# batterytester.net
KiCad netlist of a schematic drawn in EAGLE
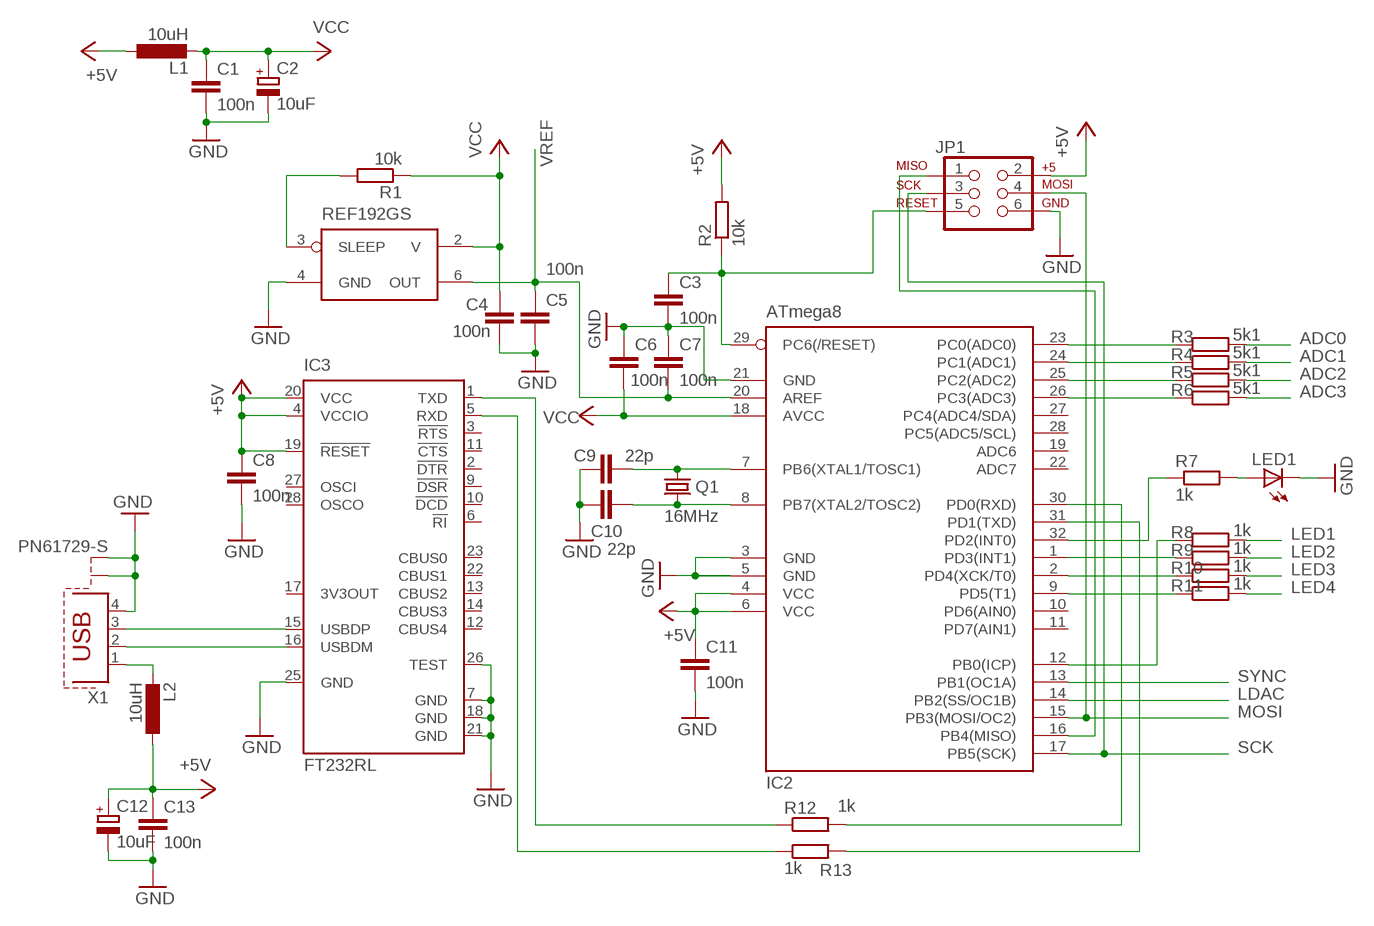
[diagram p0: schematic, sheet 1]
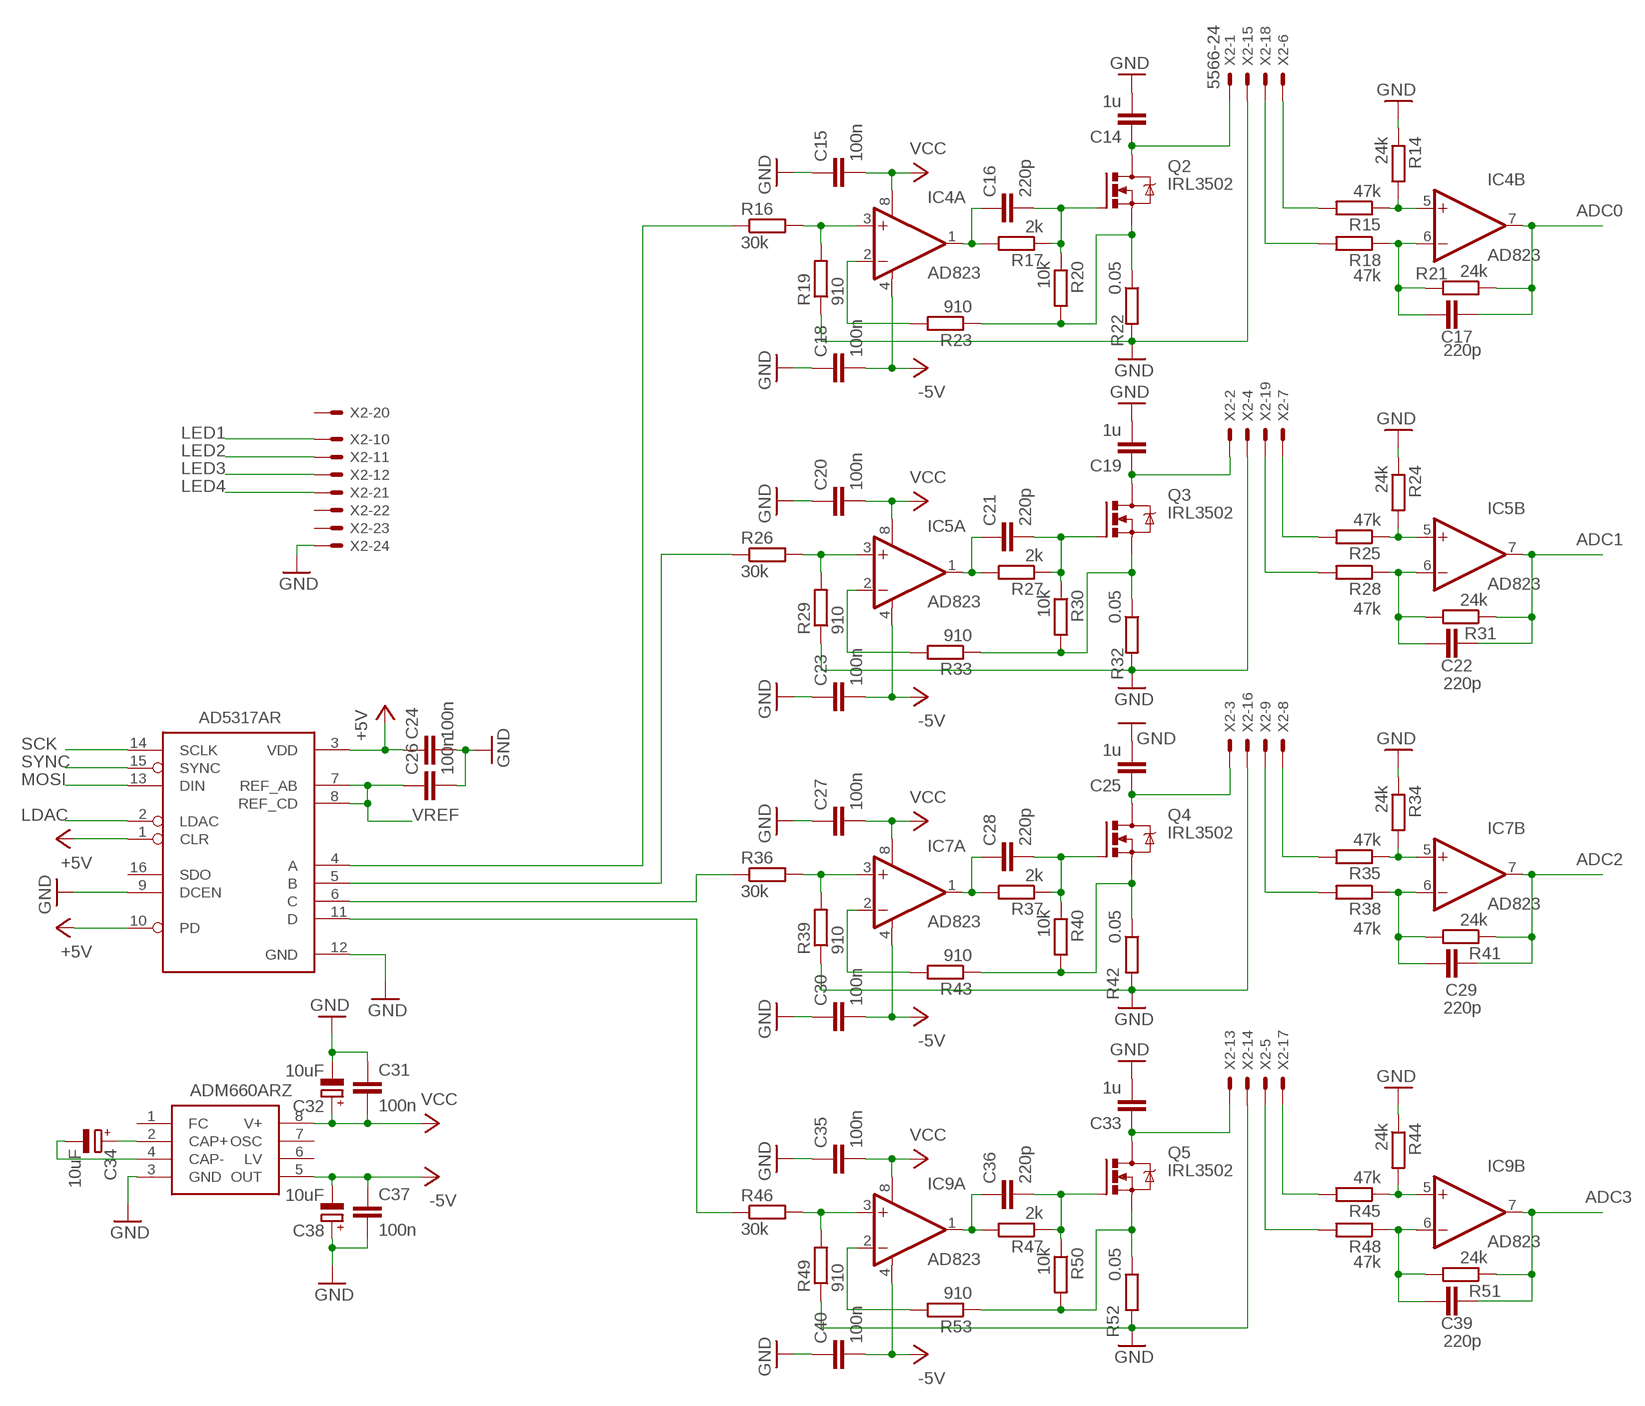
[diagram p1: schematic, sheet 2]

(export (version "E")
  (design (tool "Eeschema 10.0.6"))
  (components
    (comp (ref "C1")
      (value "100n")
      (footprint "eagle-import:C0805")
      (libsource (lib "eagle-import") (part "C-EUC0805"))
    )
    (comp (ref "C2")
      (value "10uF")
      (footprint "eagle-import:SMC_B")
      (libsource (lib "eagle-import") (part "CPOL-EUSMCB"))
    )
    (comp (ref "C3")
      (value "100n")
      (footprint "eagle-import:C0805")
      (libsource (lib "eagle-import") (part "C-EUC0805"))
    )
    (comp (ref "C4")
      (value "100n")
      (footprint "eagle-import:C0805")
      (libsource (lib "eagle-import") (part "C-EUC0805"))
    )
    (comp (ref "C5")
      (value "100n")
      (footprint "eagle-import:C0805")
      (libsource (lib "eagle-import") (part "C-EUC0805"))
    )
    (comp (ref "C6")
      (value "100n")
      (footprint "eagle-import:C0805")
      (libsource (lib "eagle-import") (part "C-EUC0805"))
    )
    (comp (ref "C7")
      (value "100n")
      (footprint "eagle-import:C0805")
      (libsource (lib "eagle-import") (part "C-EUC0805"))
    )
    (comp (ref "C8")
      (value "100n")
      (footprint "eagle-import:C0805")
      (libsource (lib "eagle-import") (part "C-EUC0805"))
    )
    (comp (ref "C9")
      (value "22p")
      (footprint "eagle-import:C0805")
      (libsource (lib "eagle-import") (part "C-EUC0805"))
    )
    (comp (ref "C10")
      (value "22p")
      (footprint "eagle-import:C0805")
      (libsource (lib "eagle-import") (part "C-EUC0805"))
    )
    (comp (ref "C11")
      (value "100n")
      (footprint "eagle-import:C0805")
      (libsource (lib "eagle-import") (part "C-EUC0805"))
    )
    (comp (ref "C12")
      (value "10uF")
      (footprint "eagle-import:SMC_B")
      (libsource (lib "eagle-import") (part "CPOL-EUSMCB"))
    )
    (comp (ref "C13")
      (value "100n")
      (footprint "eagle-import:C0805")
      (libsource (lib "eagle-import") (part "C-EUC0805"))
    )
    (comp (ref "IC1")
      (value "REF192GS")
      (footprint "eagle-import:SO8")
      (libsource (lib "eagle-import") (part "REF192"))
    )
    (comp (ref "IC2")
      (value "ATmega8")
      (footprint "eagle-import:TQFP32-08")
      (libsource (lib "eagle-import") (part "MEGA8-AI"))
    )
    (comp (ref "IC3")
      (value "FT232RL")
      (footprint "eagle-import:SSOP28")
      (libsource (lib "eagle-import") (part "FT232RL"))
    )
    (comp (ref "JP1")
      (value "AVR_SPI_PRG_6NS")
      (footprint "eagle-import:2X3-NS")
      (libsource (lib "eagle-import") (part "AVR_SPI_PRG_6NS"))
    )
    (comp (ref "L1")
      (value "10uH")
      (footprint "eagle-import:L1812")
      (libsource (lib "eagle-import") (part "L-EUL1812"))
    )
    (comp (ref "L2")
      (value "10uH")
      (footprint "eagle-import:L1812")
      (libsource (lib "eagle-import") (part "L-EUL1812"))
    )
    (comp (ref "LED1")
      (value "LED3MM")
      (footprint "eagle-import:LED3MM")
      (libsource (lib "eagle-import") (part "LED3MM"))
    )
    (comp (ref "Q1")
      (value "16MHz")
      (footprint "eagle-import:HC49_S")
      (libsource (lib "eagle-import") (part "CRYSTALHC49S"))
    )
    (comp (ref "R1")
      (value "10k")
      (footprint "eagle-import:R0805")
      (libsource (lib "eagle-import") (part "R-EU_R0805"))
    )
    (comp (ref "R2")
      (value "10k")
      (footprint "eagle-import:R0805")
      (libsource (lib "eagle-import") (part "R-EU_R0805"))
    )
    (comp (ref "R3")
      (value "5k1")
      (footprint "eagle-import:R0805")
      (libsource (lib "eagle-import") (part "R-EU_R0805"))
    )
    (comp (ref "R4")
      (value "5k1")
      (footprint "eagle-import:R0805")
      (libsource (lib "eagle-import") (part "R-EU_R0805"))
    )
    (comp (ref "R5")
      (value "5k1")
      (footprint "eagle-import:R0805")
      (libsource (lib "eagle-import") (part "R-EU_R0805"))
    )
    (comp (ref "R6")
      (value "5k1")
      (footprint "eagle-import:R0805")
      (libsource (lib "eagle-import") (part "R-EU_R0805"))
    )
    (comp (ref "R7")
      (value "1k")
      (footprint "eagle-import:R0805")
      (libsource (lib "eagle-import") (part "R-EU_R0805"))
    )
    (comp (ref "R8")
      (value "1k")
      (footprint "eagle-import:R0805")
      (libsource (lib "eagle-import") (part "R-EU_R0805"))
    )
    (comp (ref "R9")
      (value "1k")
      (footprint "eagle-import:R0805")
      (libsource (lib "eagle-import") (part "R-EU_R0805"))
    )
    (comp (ref "R10")
      (value "1k")
      (footprint "eagle-import:R0805")
      (libsource (lib "eagle-import") (part "R-EU_R0805"))
    )
    (comp (ref "R11")
      (value "1k")
      (footprint "eagle-import:R0805")
      (libsource (lib "eagle-import") (part "R-EU_R0805"))
    )
    (comp (ref "R12")
      (value "1k")
      (footprint "eagle-import:R0805")
      (libsource (lib "eagle-import") (part "R-EU_R0805"))
    )
    (comp (ref "R13")
      (value "1k")
      (footprint "eagle-import:R0805")
      (libsource (lib "eagle-import") (part "R-EU_R0805"))
    )
    (comp (ref "X1")
      (value "PN61729-S")
      (footprint "eagle-import:PN61729-S")
      (libsource (lib "eagle-import") (part "PN61729-S"))
    )
    (comp (ref "C14")
      (value "1u")
      (footprint "eagle-import:C0805")
      (libsource (lib "eagle-import") (part "C-EUC0805"))
    )
    (comp (ref "C15")
      (value "100n")
      (footprint "eagle-import:C0805")
      (libsource (lib "eagle-import") (part "C-EUC0805"))
    )
    (comp (ref "C16")
      (value "220p")
      (footprint "eagle-import:C0805")
      (libsource (lib "eagle-import") (part "C-EUC0805"))
    )
    (comp (ref "C17")
      (value "220p")
      (footprint "eagle-import:C0805")
      (libsource (lib "eagle-import") (part "C-EUC0805"))
    )
    (comp (ref "C18")
      (value "100n")
      (footprint "eagle-import:C0805")
      (libsource (lib "eagle-import") (part "C-EUC0805"))
    )
    (comp (ref "C19")
      (value "1u")
      (footprint "eagle-import:C0805")
      (libsource (lib "eagle-import") (part "C-EUC0805"))
    )
    (comp (ref "C20")
      (value "100n")
      (footprint "eagle-import:C0805")
      (libsource (lib "eagle-import") (part "C-EUC0805"))
    )
    (comp (ref "C21")
      (value "220p")
      (footprint "eagle-import:C0805")
      (libsource (lib "eagle-import") (part "C-EUC0805"))
    )
    (comp (ref "C22")
      (value "220p")
      (footprint "eagle-import:C0805")
      (libsource (lib "eagle-import") (part "C-EUC0805"))
    )
    (comp (ref "C23")
      (value "100n")
      (footprint "eagle-import:C0805")
      (libsource (lib "eagle-import") (part "C-EUC0805"))
    )
    (comp (ref "C24")
      (value "100n")
      (footprint "eagle-import:C0805")
      (libsource (lib "eagle-import") (part "C-EUC0805"))
    )
    (comp (ref "C25")
      (value "1u")
      (footprint "eagle-import:C0805")
      (libsource (lib "eagle-import") (part "C-EUC0805"))
    )
    (comp (ref "C26")
      (value "100n")
      (footprint "eagle-import:C0805")
      (libsource (lib "eagle-import") (part "C-EUC0805"))
    )
    (comp (ref "C27")
      (value "100n")
      (footprint "eagle-import:C0805")
      (libsource (lib "eagle-import") (part "C-EUC0805"))
    )
    (comp (ref "C28")
      (value "220p")
      (footprint "eagle-import:C0805")
      (libsource (lib "eagle-import") (part "C-EUC0805"))
    )
    (comp (ref "C29")
      (value "220p")
      (footprint "eagle-import:C0805")
      (libsource (lib "eagle-import") (part "C-EUC0805"))
    )
    (comp (ref "C30")
      (value "100n")
      (footprint "eagle-import:C0805")
      (libsource (lib "eagle-import") (part "C-EUC0805"))
    )
    (comp (ref "C31")
      (value "100n")
      (footprint "eagle-import:C0805")
      (libsource (lib "eagle-import") (part "C-EUC0805"))
    )
    (comp (ref "C32")
      (value "10uF")
      (footprint "eagle-import:SMC_B")
      (libsource (lib "eagle-import") (part "CPOL-EUSMCB"))
    )
    (comp (ref "C33")
      (value "1u")
      (footprint "eagle-import:C0805")
      (libsource (lib "eagle-import") (part "C-EUC0805"))
    )
    (comp (ref "C34")
      (value "10uF")
      (footprint "eagle-import:SMC_B")
      (libsource (lib "eagle-import") (part "CPOL-EUSMCB"))
    )
    (comp (ref "C35")
      (value "100n")
      (footprint "eagle-import:C0805")
      (libsource (lib "eagle-import") (part "C-EUC0805"))
    )
    (comp (ref "C36")
      (value "220p")
      (footprint "eagle-import:C0805")
      (libsource (lib "eagle-import") (part "C-EUC0805"))
    )
    (comp (ref "C37")
      (value "100n")
      (footprint "eagle-import:C0805")
      (libsource (lib "eagle-import") (part "C-EUC0805"))
    )
    (comp (ref "C38")
      (value "10uF")
      (footprint "eagle-import:SMC_B")
      (libsource (lib "eagle-import") (part "CPOL-EUSMCB"))
    )
    (comp (ref "C39")
      (value "220p")
      (footprint "eagle-import:C0805")
      (libsource (lib "eagle-import") (part "C-EUC0805"))
    )
    (comp (ref "C40")
      (value "100n")
      (footprint "eagle-import:C0805")
      (libsource (lib "eagle-import") (part "C-EUC0805"))
    )
    (comp (ref "IC4")
      (value "AD823")
      (footprint "eagle-import:SO8")
      (libsource (lib "eagle-import") (part "AD823"))
    )
    (comp (ref "IC5")
      (value "AD823")
      (footprint "eagle-import:SO8")
      (libsource (lib "eagle-import") (part "AD823"))
    )
    (comp (ref "IC6")
      (value "AD5317AR")
      (footprint "eagle-import:TSSOP16")
      (libsource (lib "eagle-import") (part "AD5317"))
    )
    (comp (ref "IC7")
      (value "AD823")
      (footprint "eagle-import:SO8")
      (libsource (lib "eagle-import") (part "AD823"))
    )
    (comp (ref "IC8")
      (value "ADM660ARZ")
      (footprint "eagle-import:SO8")
      (libsource (lib "eagle-import") (part "ADM660"))
    )
    (comp (ref "IC9")
      (value "AD823")
      (footprint "eagle-import:SO8")
      (libsource (lib "eagle-import") (part "AD823"))
    )
    (comp (ref "Q2")
      (value "IRL3502")
      (footprint "eagle-import:TO220BV")
      (libsource (lib "eagle-import") (part "IRF540"))
    )
    (comp (ref "Q3")
      (value "IRL3502")
      (footprint "eagle-import:TO220BV")
      (libsource (lib "eagle-import") (part "IRF540"))
    )
    (comp (ref "Q4")
      (value "IRL3502")
      (footprint "eagle-import:TO220BV")
      (libsource (lib "eagle-import") (part "IRF540"))
    )
    (comp (ref "Q5")
      (value "IRL3502")
      (footprint "eagle-import:TO220BV")
      (libsource (lib "eagle-import") (part "IRF540"))
    )
    (comp (ref "R14")
      (value "24k")
      (footprint "eagle-import:R0805")
      (libsource (lib "eagle-import") (part "R-EU_R0805"))
    )
    (comp (ref "R15")
      (value "47k")
      (footprint "eagle-import:R0805")
      (libsource (lib "eagle-import") (part "R-EU_R0805"))
    )
    (comp (ref "R16")
      (value "30k")
      (footprint "eagle-import:R0805")
      (libsource (lib "eagle-import") (part "R-EU_R0805"))
    )
    (comp (ref "R17")
      (value "2k")
      (footprint "eagle-import:R0805")
      (libsource (lib "eagle-import") (part "R-EU_R0805"))
    )
    (comp (ref "R18")
      (value "47k")
      (footprint "eagle-import:R0805")
      (libsource (lib "eagle-import") (part "R-EU_R0805"))
    )
    (comp (ref "R19")
      (value "910")
      (footprint "eagle-import:R0805")
      (libsource (lib "eagle-import") (part "R-EU_R0805"))
    )
    (comp (ref "R20")
      (value "10k")
      (footprint "eagle-import:R0805")
      (libsource (lib "eagle-import") (part "R-EU_R0805"))
    )
    (comp (ref "R21")
      (value "24k")
      (footprint "eagle-import:R0805")
      (libsource (lib "eagle-import") (part "R-EU_R0805"))
    )
    (comp (ref "R22")
      (value "0.05")
      (footprint "eagle-import:R2512")
      (libsource (lib "eagle-import") (part "R-EU_R2512"))
    )
    (comp (ref "R23")
      (value "910")
      (footprint "eagle-import:R0805")
      (libsource (lib "eagle-import") (part "R-EU_R0805"))
    )
    (comp (ref "R24")
      (value "24k")
      (footprint "eagle-import:R0805")
      (libsource (lib "eagle-import") (part "R-EU_R0805"))
    )
    (comp (ref "R25")
      (value "47k")
      (footprint "eagle-import:R0805")
      (libsource (lib "eagle-import") (part "R-EU_R0805"))
    )
    (comp (ref "R26")
      (value "30k")
      (footprint "eagle-import:R0805")
      (libsource (lib "eagle-import") (part "R-EU_R0805"))
    )
    (comp (ref "R27")
      (value "2k")
      (footprint "eagle-import:R0805")
      (libsource (lib "eagle-import") (part "R-EU_R0805"))
    )
    (comp (ref "R28")
      (value "47k")
      (footprint "eagle-import:R0805")
      (libsource (lib "eagle-import") (part "R-EU_R0805"))
    )
    (comp (ref "R29")
      (value "910")
      (footprint "eagle-import:R0805")
      (libsource (lib "eagle-import") (part "R-EU_R0805"))
    )
    (comp (ref "R30")
      (value "10k")
      (footprint "eagle-import:R0805")
      (libsource (lib "eagle-import") (part "R-EU_R0805"))
    )
    (comp (ref "R31")
      (value "24k")
      (footprint "eagle-import:R0805")
      (libsource (lib "eagle-import") (part "R-EU_R0805"))
    )
    (comp (ref "R32")
      (value "0.05")
      (footprint "eagle-import:R2512")
      (libsource (lib "eagle-import") (part "R-EU_R2512"))
    )
    (comp (ref "R33")
      (value "910")
      (footprint "eagle-import:R0805")
      (libsource (lib "eagle-import") (part "R-EU_R0805"))
    )
    (comp (ref "R34")
      (value "24k")
      (footprint "eagle-import:R0805")
      (libsource (lib "eagle-import") (part "R-EU_R0805"))
    )
    (comp (ref "R35")
      (value "47k")
      (footprint "eagle-import:R0805")
      (libsource (lib "eagle-import") (part "R-EU_R0805"))
    )
    (comp (ref "R36")
      (value "30k")
      (footprint "eagle-import:R0805")
      (libsource (lib "eagle-import") (part "R-EU_R0805"))
    )
    (comp (ref "R37")
      (value "2k")
      (footprint "eagle-import:R0805")
      (libsource (lib "eagle-import") (part "R-EU_R0805"))
    )
    (comp (ref "R38")
      (value "47k")
      (footprint "eagle-import:R0805")
      (libsource (lib "eagle-import") (part "R-EU_R0805"))
    )
    (comp (ref "R39")
      (value "910")
      (footprint "eagle-import:R0805")
      (libsource (lib "eagle-import") (part "R-EU_R0805"))
    )
    (comp (ref "R40")
      (value "10k")
      (footprint "eagle-import:R0805")
      (libsource (lib "eagle-import") (part "R-EU_R0805"))
    )
    (comp (ref "R41")
      (value "24k")
      (footprint "eagle-import:R0805")
      (libsource (lib "eagle-import") (part "R-EU_R0805"))
    )
    (comp (ref "R42")
      (value "0.05")
      (footprint "eagle-import:R2512")
      (libsource (lib "eagle-import") (part "R-EU_R2512"))
    )
    (comp (ref "R43")
      (value "910")
      (footprint "eagle-import:R0805")
      (libsource (lib "eagle-import") (part "R-EU_R0805"))
    )
    (comp (ref "R44")
      (value "24k")
      (footprint "eagle-import:R0805")
      (libsource (lib "eagle-import") (part "R-EU_R0805"))
    )
    (comp (ref "R45")
      (value "47k")
      (footprint "eagle-import:R0805")
      (libsource (lib "eagle-import") (part "R-EU_R0805"))
    )
    (comp (ref "R46")
      (value "30k")
      (footprint "eagle-import:R0805")
      (libsource (lib "eagle-import") (part "R-EU_R0805"))
    )
    (comp (ref "R47")
      (value "2k")
      (footprint "eagle-import:R0805")
      (libsource (lib "eagle-import") (part "R-EU_R0805"))
    )
    (comp (ref "R48")
      (value "47k")
      (footprint "eagle-import:R0805")
      (libsource (lib "eagle-import") (part "R-EU_R0805"))
    )
    (comp (ref "R49")
      (value "910")
      (footprint "eagle-import:R0805")
      (libsource (lib "eagle-import") (part "R-EU_R0805"))
    )
    (comp (ref "R50")
      (value "10k")
      (footprint "eagle-import:R0805")
      (libsource (lib "eagle-import") (part "R-EU_R0805"))
    )
    (comp (ref "R51")
      (value "24k")
      (footprint "eagle-import:R0805")
      (libsource (lib "eagle-import") (part "R-EU_R0805"))
    )
    (comp (ref "R52")
      (value "0.05")
      (footprint "eagle-import:R2512")
      (libsource (lib "eagle-import") (part "R-EU_R2512"))
    )
    (comp (ref "R53")
      (value "910")
      (footprint "eagle-import:R0805")
      (libsource (lib "eagle-import") (part "R-EU_R0805"))
    )
    (comp (ref "X2")
      (value "5566-24")
      (footprint "eagle-import:5569-24")
      (libsource (lib "eagle-import") (part "5566-245569-24"))
    )
  )
  (nets
    (net (code "1") (name "+5V") (class "Default")
      (node (ref "C11") (pin "1") (pinfunction "1_1") (pintype "passive"))
      (node (ref "C12") (pin "+") (pinfunction "+_+") (pintype "passive"))
      (node (ref "C13") (pin "1") (pinfunction "1_1") (pintype "passive"))
      (node (ref "C24") (pin "1") (pinfunction "1_1") (pintype "passive"))
      (node (ref "C8") (pin "1") (pinfunction "1_1") (pintype "passive"))
      (node (ref "IC2") (pin "4") (pinfunction "VCC_4") (pintype "power_in"))
      (node (ref "IC2") (pin "6") (pinfunction "VCC_6") (pintype "power_in"))
      (node (ref "IC3") (pin "19") (pinfunction "~{RESET}_19") (pintype "input"))
      (node (ref "IC3") (pin "20") (pinfunction "VCC_20") (pintype "power_in"))
      (node (ref "IC3") (pin "4") (pinfunction "VCCIO_4") (pintype "power_in"))
      (node (ref "IC6") (pin "1") (pinfunction "CLR_1") (pintype "bidirectional"))
      (node (ref "IC6") (pin "10") (pinfunction "PD_10") (pintype "bidirectional"))
      (node (ref "IC6") (pin "3") (pinfunction "VDD_3") (pintype "bidirectional"))
      (node (ref "JP1") (pin "2") (pinfunction "2_2") (pintype "passive"))
      (node (ref "L1") (pin "1") (pinfunction "1_1") (pintype "passive"))
      (node (ref "L2") (pin "1") (pinfunction "1_1") (pintype "passive"))
      (node (ref "R2") (pin "2") (pinfunction "2_2") (pintype "passive"))
    )
    (net (code "2") (name "-5V") (class "Default")
      (node (ref "C18") (pin "2") (pinfunction "2_2") (pintype "passive"))
      (node (ref "C23") (pin "2") (pinfunction "2_2") (pintype "passive"))
      (node (ref "C30") (pin "2") (pinfunction "2_2") (pintype "passive"))
      (node (ref "C37") (pin "1") (pinfunction "1_1") (pintype "passive"))
      (node (ref "C38") (pin "-") (pinfunction "-_-") (pintype "passive"))
      (node (ref "C40") (pin "2") (pinfunction "2_2") (pintype "passive"))
      (node (ref "IC4") (pin "4") (pinfunction "V-_4") (pintype "power_in"))
      (node (ref "IC5") (pin "4") (pinfunction "V-_4") (pintype "power_in"))
      (node (ref "IC7") (pin "4") (pinfunction "V-_4") (pintype "power_in"))
      (node (ref "IC8") (pin "5") (pinfunction "OUT_5") (pintype "bidirectional"))
      (node (ref "IC9") (pin "4") (pinfunction "V-_4") (pintype "power_in"))
    )
    (net (code "3") (name "ADC0") (class "Default")
      (node (ref "C17") (pin "2") (pinfunction "2_2") (pintype "passive"))
      (node (ref "IC4") (pin "7") (pinfunction "OUT_7") (pintype "output"))
      (node (ref "R21") (pin "1") (pinfunction "1_1") (pintype "passive"))
      (node (ref "R3") (pin "2") (pinfunction "2_2") (pintype "passive"))
    )
    (net (code "4") (name "ADC1") (class "Default")
      (node (ref "C22") (pin "2") (pinfunction "2_2") (pintype "passive"))
      (node (ref "IC5") (pin "7") (pinfunction "OUT_7") (pintype "output"))
      (node (ref "R31") (pin "1") (pinfunction "1_1") (pintype "passive"))
      (node (ref "R4") (pin "2") (pinfunction "2_2") (pintype "passive"))
    )
    (net (code "5") (name "ADC2") (class "Default")
      (node (ref "C29") (pin "2") (pinfunction "2_2") (pintype "passive"))
      (node (ref "IC7") (pin "7") (pinfunction "OUT_7") (pintype "output"))
      (node (ref "R41") (pin "1") (pinfunction "1_1") (pintype "passive"))
      (node (ref "R5") (pin "2") (pinfunction "2_2") (pintype "passive"))
    )
    (net (code "6") (name "ADC3") (class "Default")
      (node (ref "C39") (pin "2") (pinfunction "2_2") (pintype "passive"))
      (node (ref "IC9") (pin "7") (pinfunction "OUT_7") (pintype "output"))
      (node (ref "R51") (pin "1") (pinfunction "1_1") (pintype "passive"))
      (node (ref "R6") (pin "2") (pinfunction "2_2") (pintype "passive"))
    )
    (net (code "7") (name "GND") (class "Default")
      (node (ref "C1") (pin "2") (pinfunction "2_2") (pintype "passive"))
      (node (ref "C10") (pin "1") (pinfunction "1_1") (pintype "passive"))
      (node (ref "C11") (pin "2") (pinfunction "2_2") (pintype "passive"))
      (node (ref "C12") (pin "-") (pinfunction "-_-") (pintype "passive"))
      (node (ref "C13") (pin "2") (pinfunction "2_2") (pintype "passive"))
      (node (ref "C14") (pin "2") (pinfunction "2_2") (pintype "passive"))
      (node (ref "C15") (pin "1") (pinfunction "1_1") (pintype "passive"))
      (node (ref "C18") (pin "1") (pinfunction "1_1") (pintype "passive"))
      (node (ref "C19") (pin "2") (pinfunction "2_2") (pintype "passive"))
      (node (ref "C2") (pin "-") (pinfunction "-_-") (pintype "passive"))
      (node (ref "C20") (pin "1") (pinfunction "1_1") (pintype "passive"))
      (node (ref "C23") (pin "1") (pinfunction "1_1") (pintype "passive"))
      (node (ref "C24") (pin "2") (pinfunction "2_2") (pintype "passive"))
      (node (ref "C25") (pin "2") (pinfunction "2_2") (pintype "passive"))
      (node (ref "C26") (pin "2") (pinfunction "2_2") (pintype "passive"))
      (node (ref "C27") (pin "1") (pinfunction "1_1") (pintype "passive"))
      (node (ref "C3") (pin "2") (pinfunction "2_2") (pintype "passive"))
      (node (ref "C30") (pin "1") (pinfunction "1_1") (pintype "passive"))
      (node (ref "C31") (pin "1") (pinfunction "1_1") (pintype "passive"))
      (node (ref "C32") (pin "-") (pinfunction "-_-") (pintype "passive"))
      (node (ref "C33") (pin "2") (pinfunction "2_2") (pintype "passive"))
      (node (ref "C35") (pin "1") (pinfunction "1_1") (pintype "passive"))
      (node (ref "C37") (pin "2") (pinfunction "2_2") (pintype "passive"))
      (node (ref "C38") (pin "+") (pinfunction "+_+") (pintype "passive"))
      (node (ref "C4") (pin "2") (pinfunction "2_2") (pintype "passive"))
      (node (ref "C40") (pin "1") (pinfunction "1_1") (pintype "passive"))
      (node (ref "C5") (pin "2") (pinfunction "2_2") (pintype "passive"))
      (node (ref "C6") (pin "1") (pinfunction "1_1") (pintype "passive"))
      (node (ref "C7") (pin "1") (pinfunction "1_1") (pintype "passive"))
      (node (ref "C8") (pin "2") (pinfunction "2_2") (pintype "passive"))
      (node (ref "C9") (pin "1") (pinfunction "1_1") (pintype "passive"))
      (node (ref "IC1") (pin "4") (pinfunction "GND_4") (pintype "power_in"))
      (node (ref "IC2") (pin "21") (pinfunction "GND_21") (pintype "power_in"))
      (node (ref "IC2") (pin "3") (pinfunction "GND_3") (pintype "power_in"))
      (node (ref "IC2") (pin "5") (pinfunction "GND_5") (pintype "power_in"))
      (node (ref "IC3") (pin "18") (pinfunction "GND_18") (pintype "power_in"))
      (node (ref "IC3") (pin "21") (pinfunction "GND_21") (pintype "power_in"))
      (node (ref "IC3") (pin "25") (pinfunction "GND_25") (pintype "power_in"))
      (node (ref "IC3") (pin "26") (pinfunction "TEST_26") (pintype "input"))
      (node (ref "IC3") (pin "7") (pinfunction "GND_7") (pintype "power_in"))
      (node (ref "IC6") (pin "12") (pinfunction "GND_12") (pintype "bidirectional"))
      (node (ref "IC6") (pin "9") (pinfunction "DCEN_9") (pintype "bidirectional"))
      (node (ref "IC8") (pin "3") (pinfunction "GND_3") (pintype "bidirectional"))
      (node (ref "JP1") (pin "6") (pinfunction "6_6") (pintype "passive"))
      (node (ref "LED1") (pin "K") (pinfunction "C_K") (pintype "passive"))
      (node (ref "R14") (pin "1") (pinfunction "1_1") (pintype "passive"))
      (node (ref "R19") (pin "1") (pinfunction "1_1") (pintype "passive"))
      (node (ref "R22") (pin "2") (pinfunction "2_2") (pintype "passive"))
      (node (ref "R24") (pin "1") (pinfunction "1_1") (pintype "passive"))
      (node (ref "R29") (pin "1") (pinfunction "1_1") (pintype "passive"))
      (node (ref "R32") (pin "2") (pinfunction "2_2") (pintype "passive"))
      (node (ref "R34") (pin "1") (pinfunction "1_1") (pintype "passive"))
      (node (ref "R39") (pin "1") (pinfunction "1_1") (pintype "passive"))
      (node (ref "R42") (pin "2") (pinfunction "2_2") (pintype "passive"))
      (node (ref "R44") (pin "1") (pinfunction "1_1") (pintype "passive"))
      (node (ref "R49") (pin "1") (pinfunction "1_1") (pintype "passive"))
      (node (ref "R52") (pin "2") (pinfunction "2_2") (pintype "passive"))
      (node (ref "X1") (pin "4") (pinfunction "4_4") (pintype "passive"))
      (node (ref "X1") (pin "S1") (pinfunction "S1_S1") (pintype "passive"))
      (node (ref "X1") (pin "S2") (pinfunction "S2_S2") (pintype "passive"))
      (node (ref "X2") (pin "14") (pinfunction "S_14") (pintype "passive"))
      (node (ref "X2") (pin "15") (pinfunction "S_15") (pintype "passive"))
      (node (ref "X2") (pin "16") (pinfunction "S_16") (pintype "passive"))
      (node (ref "X2") (pin "24") (pinfunction "S_24") (pintype "passive"))
      (node (ref "X2") (pin "4") (pinfunction "S_4") (pintype "passive"))
    )
    (net (code "8") (name "LDAC") (class "Default")
      (node (ref "IC2") (pin "14") (pinfunction "PB2(SS/OC1B)_14") (pintype "bidirectional"))
      (node (ref "IC6") (pin "2") (pinfunction "LDAC_2") (pintype "bidirectional"))
    )
    (net (code "9") (name "LED1") (class "Default")
      (node (ref "R8") (pin "2") (pinfunction "2_2") (pintype "passive"))
      (node (ref "X2") (pin "10") (pinfunction "S_10") (pintype "passive"))
    )
    (net (code "10") (name "LED2") (class "Default")
      (node (ref "R9") (pin "2") (pinfunction "2_2") (pintype "passive"))
      (node (ref "X2") (pin "11") (pinfunction "S_11") (pintype "passive"))
    )
    (net (code "11") (name "LED3") (class "Default")
      (node (ref "R10") (pin "2") (pinfunction "2_2") (pintype "passive"))
      (node (ref "X2") (pin "12") (pinfunction "S_12") (pintype "passive"))
    )
    (net (code "12") (name "LED4") (class "Default")
      (node (ref "R11") (pin "2") (pinfunction "2_2") (pintype "passive"))
      (node (ref "X2") (pin "21") (pinfunction "S_21") (pintype "passive"))
    )
    (net (code "13") (name "MOSI") (class "Default")
      (node (ref "IC2") (pin "15") (pinfunction "PB3(MOSI/OC2)_15") (pintype "bidirectional"))
      (node (ref "IC6") (pin "13") (pinfunction "DIN_13") (pintype "bidirectional"))
      (node (ref "JP1") (pin "4") (pinfunction "4_4") (pintype "passive"))
    )
    (net (code "14") (name "Net-(C16-Pad2)") (class "Default")
      (node (ref "C16") (pin "2") (pinfunction "2_2") (pintype "passive"))
      (node (ref "Q2") (pin "G") (pinfunction "G_G") (pintype "passive"))
      (node (ref "R17") (pin "1") (pinfunction "1_1") (pintype "passive"))
      (node (ref "R20") (pin "1") (pinfunction "1_1") (pintype "passive"))
    )
    (net (code "15") (name "Net-(C21-Pad2)") (class "Default")
      (node (ref "C21") (pin "2") (pinfunction "2_2") (pintype "passive"))
      (node (ref "Q3") (pin "G") (pinfunction "G_G") (pintype "passive"))
      (node (ref "R27") (pin "1") (pinfunction "1_1") (pintype "passive"))
      (node (ref "R30") (pin "1") (pinfunction "1_1") (pintype "passive"))
    )
    (net (code "16") (name "Net-(C28-Pad2)") (class "Default")
      (node (ref "C28") (pin "2") (pinfunction "2_2") (pintype "passive"))
      (node (ref "Q4") (pin "G") (pinfunction "G_G") (pintype "passive"))
      (node (ref "R37") (pin "1") (pinfunction "1_1") (pintype "passive"))
      (node (ref "R40") (pin "1") (pinfunction "1_1") (pintype "passive"))
    )
    (net (code "17") (name "Net-(C36-Pad2)") (class "Default")
      (node (ref "C36") (pin "2") (pinfunction "2_2") (pintype "passive"))
      (node (ref "Q5") (pin "G") (pinfunction "G_G") (pintype "passive"))
      (node (ref "R47") (pin "1") (pinfunction "1_1") (pintype "passive"))
      (node (ref "R50") (pin "1") (pinfunction "1_1") (pintype "passive"))
    )
    (net (code "18") (name "Net-(IC1-SLEEP)") (class "Default")
      (node (ref "IC1") (pin "3") (pinfunction "SLEEP_3") (pintype "input"))
      (node (ref "R1") (pin "2") (pinfunction "2_2") (pintype "passive"))
    )
    (net (code "19") (name "Net-(IC2-PB0(ICP))") (class "Default")
      (node (ref "IC2") (pin "12") (pinfunction "PB0(ICP)_12") (pintype "bidirectional"))
      (node (ref "R8") (pin "1") (pinfunction "1_1") (pintype "passive"))
    )
    (net (code "20") (name "Net-(IC2-PB4(MISO))") (class "Default")
      (node (ref "IC2") (pin "16") (pinfunction "PB4(MISO)_16") (pintype "bidirectional"))
      (node (ref "JP1") (pin "1") (pinfunction "1_1") (pintype "passive"))
    )
    (net (code "21") (name "Net-(IC2-PB6(XTAL1{slash}TOSC1))") (class "Default")
      (node (ref "C9") (pin "2") (pinfunction "2_2") (pintype "passive"))
      (node (ref "IC2") (pin "7") (pinfunction "PB6(XTAL1/TOSC1)_7") (pintype "bidirectional"))
      (node (ref "Q1") (pin "1") (pinfunction "1_1") (pintype "passive"))
    )
    (net (code "22") (name "Net-(IC2-PB7(XTAL2{slash}TOSC2))") (class "Default")
      (node (ref "C10") (pin "2") (pinfunction "2_2") (pintype "passive"))
      (node (ref "IC2") (pin "8") (pinfunction "PB7(XTAL2/TOSC2)_8") (pintype "bidirectional"))
      (node (ref "Q1") (pin "2") (pinfunction "2_2") (pintype "passive"))
    )
    (net (code "23") (name "Net-(IC2-PC0(ADC0))") (class "Default")
      (node (ref "IC2") (pin "23") (pinfunction "PC0(ADC0)_23") (pintype "bidirectional"))
      (node (ref "R3") (pin "1") (pinfunction "1_1") (pintype "passive"))
    )
    (net (code "24") (name "Net-(IC2-PC1(ADC1))") (class "Default")
      (node (ref "IC2") (pin "24") (pinfunction "PC1(ADC1)_24") (pintype "bidirectional"))
      (node (ref "R4") (pin "1") (pinfunction "1_1") (pintype "passive"))
    )
    (net (code "25") (name "Net-(IC2-PC2(ADC2))") (class "Default")
      (node (ref "IC2") (pin "25") (pinfunction "PC2(ADC2)_25") (pintype "bidirectional"))
      (node (ref "R5") (pin "1") (pinfunction "1_1") (pintype "passive"))
    )
    (net (code "26") (name "Net-(IC2-PC3(ADC3))") (class "Default")
      (node (ref "IC2") (pin "26") (pinfunction "PC3(ADC3)_26") (pintype "bidirectional"))
      (node (ref "R6") (pin "1") (pinfunction "1_1") (pintype "passive"))
    )
    (net (code "27") (name "Net-(IC2-PC6({slash}RESET))") (class "Default")
      (node (ref "C3") (pin "1") (pinfunction "1_1") (pintype "passive"))
      (node (ref "IC2") (pin "29") (pinfunction "PC6(/RESET)_29") (pintype "bidirectional"))
      (node (ref "JP1") (pin "5") (pinfunction "5_5") (pintype "passive"))
      (node (ref "R2") (pin "1") (pinfunction "1_1") (pintype "passive"))
    )
    (net (code "28") (name "Net-(IC2-PD0(RXD))") (class "Default")
      (node (ref "IC2") (pin "30") (pinfunction "PD0(RXD)_30") (pintype "bidirectional"))
      (node (ref "R12") (pin "2") (pinfunction "2_2") (pintype "passive"))
    )
    (net (code "29") (name "Net-(IC2-PD1(TXD))") (class "Default")
      (node (ref "IC2") (pin "31") (pinfunction "PD1(TXD)_31") (pintype "bidirectional"))
      (node (ref "R13") (pin "2") (pinfunction "2_2") (pintype "passive"))
    )
    (net (code "30") (name "Net-(IC2-PD2(INT0))") (class "Default")
      (node (ref "IC2") (pin "32") (pinfunction "PD2(INT0)_32") (pintype "bidirectional"))
      (node (ref "R7") (pin "1") (pinfunction "1_1") (pintype "passive"))
    )
    (net (code "31") (name "Net-(IC2-PD3(INT1))") (class "Default")
      (node (ref "IC2") (pin "1") (pinfunction "PD3(INT1)_1") (pintype "bidirectional"))
      (node (ref "R9") (pin "1") (pinfunction "1_1") (pintype "passive"))
    )
    (net (code "32") (name "Net-(IC2-PD4(XCK{slash}T0))") (class "Default")
      (node (ref "IC2") (pin "2") (pinfunction "PD4(XCK/T0)_2") (pintype "bidirectional"))
      (node (ref "R10") (pin "1") (pinfunction "1_1") (pintype "passive"))
    )
    (net (code "33") (name "Net-(IC2-PD5(T1))") (class "Default")
      (node (ref "IC2") (pin "9") (pinfunction "PD5(T1)_9") (pintype "bidirectional"))
      (node (ref "R11") (pin "1") (pinfunction "1_1") (pintype "passive"))
    )
    (net (code "34") (name "Net-(IC3-RXD)") (class "Default")
      (node (ref "IC3") (pin "5") (pinfunction "RXD_5") (pintype "input"))
      (node (ref "R13") (pin "1") (pinfunction "1_1") (pintype "passive"))
    )
    (net (code "35") (name "Net-(IC3-TXD)") (class "Default")
      (node (ref "IC3") (pin "1") (pinfunction "TXD_1") (pintype "output"))
      (node (ref "R12") (pin "1") (pinfunction "1_1") (pintype "passive"))
    )
    (net (code "36") (name "Net-(IC3-USBDM)") (class "Default")
      (node (ref "IC3") (pin "16") (pinfunction "USBDM_16") (pintype "bidirectional"))
      (node (ref "X1") (pin "2") (pinfunction "2_2") (pintype "passive"))
    )
    (net (code "37") (name "Net-(IC3-USBDP)") (class "Default")
      (node (ref "IC3") (pin "15") (pinfunction "USBDP_15") (pintype "bidirectional"))
      (node (ref "X1") (pin "3") (pinfunction "3_3") (pintype "passive"))
    )
    (net (code "38") (name "Net-(IC4A-+IN)") (class "Default")
      (node (ref "IC4") (pin "3") (pinfunction "+IN_3") (pintype "input"))
      (node (ref "R16") (pin "2") (pinfunction "2_2") (pintype "passive"))
      (node (ref "R19") (pin "2") (pinfunction "2_2") (pintype "passive"))
    )
    (net (code "39") (name "Net-(IC4A--IN)") (class "Default")
      (node (ref "IC4") (pin "2") (pinfunction "-IN_2") (pintype "input"))
      (node (ref "R23") (pin "2") (pinfunction "2_2") (pintype "passive"))
    )
    (net (code "40") (name "Net-(IC4A-OUT)") (class "Default")
      (node (ref "C16") (pin "1") (pinfunction "1_1") (pintype "passive"))
      (node (ref "IC4") (pin "1") (pinfunction "OUT_1") (pintype "output"))
      (node (ref "R17") (pin "2") (pinfunction "2_2") (pintype "passive"))
    )
    (net (code "41") (name "Net-(IC4B-+IN)") (class "Default")
      (node (ref "IC4") (pin "5") (pinfunction "+IN_5") (pintype "input"))
      (node (ref "R14") (pin "2") (pinfunction "2_2") (pintype "passive"))
      (node (ref "R15") (pin "1") (pinfunction "1_1") (pintype "passive"))
    )
    (net (code "42") (name "Net-(IC4B--IN)") (class "Default")
      (node (ref "C17") (pin "1") (pinfunction "1_1") (pintype "passive"))
      (node (ref "IC4") (pin "6") (pinfunction "-IN_6") (pintype "input"))
      (node (ref "R18") (pin "1") (pinfunction "1_1") (pintype "passive"))
      (node (ref "R21") (pin "2") (pinfunction "2_2") (pintype "passive"))
    )
    (net (code "43") (name "Net-(IC5A-+IN)") (class "Default")
      (node (ref "IC5") (pin "3") (pinfunction "+IN_3") (pintype "input"))
      (node (ref "R26") (pin "2") (pinfunction "2_2") (pintype "passive"))
      (node (ref "R29") (pin "2") (pinfunction "2_2") (pintype "passive"))
    )
    (net (code "44") (name "Net-(IC5A--IN)") (class "Default")
      (node (ref "IC5") (pin "2") (pinfunction "-IN_2") (pintype "input"))
      (node (ref "R33") (pin "2") (pinfunction "2_2") (pintype "passive"))
    )
    (net (code "45") (name "Net-(IC5A-OUT)") (class "Default")
      (node (ref "C21") (pin "1") (pinfunction "1_1") (pintype "passive"))
      (node (ref "IC5") (pin "1") (pinfunction "OUT_1") (pintype "output"))
      (node (ref "R27") (pin "2") (pinfunction "2_2") (pintype "passive"))
    )
    (net (code "46") (name "Net-(IC5B-+IN)") (class "Default")
      (node (ref "IC5") (pin "5") (pinfunction "+IN_5") (pintype "input"))
      (node (ref "R24") (pin "2") (pinfunction "2_2") (pintype "passive"))
      (node (ref "R25") (pin "1") (pinfunction "1_1") (pintype "passive"))
    )
    (net (code "47") (name "Net-(IC5B--IN)") (class "Default")
      (node (ref "C22") (pin "1") (pinfunction "1_1") (pintype "passive"))
      (node (ref "IC5") (pin "6") (pinfunction "-IN_6") (pintype "input"))
      (node (ref "R28") (pin "1") (pinfunction "1_1") (pintype "passive"))
      (node (ref "R31") (pin "2") (pinfunction "2_2") (pintype "passive"))
    )
    (net (code "48") (name "Net-(IC6-A)") (class "Default")
      (node (ref "IC6") (pin "4") (pinfunction "A_4") (pintype "bidirectional"))
      (node (ref "R16") (pin "1") (pinfunction "1_1") (pintype "passive"))
    )
    (net (code "49") (name "Net-(IC6-B)") (class "Default")
      (node (ref "IC6") (pin "5") (pinfunction "B_5") (pintype "bidirectional"))
      (node (ref "R26") (pin "1") (pinfunction "1_1") (pintype "passive"))
    )
    (net (code "50") (name "Net-(IC6-C)") (class "Default")
      (node (ref "IC6") (pin "6") (pinfunction "C_6") (pintype "bidirectional"))
      (node (ref "R36") (pin "1") (pinfunction "1_1") (pintype "passive"))
    )
    (net (code "51") (name "Net-(IC6-D)") (class "Default")
      (node (ref "IC6") (pin "11") (pinfunction "D_11") (pintype "bidirectional"))
      (node (ref "R46") (pin "1") (pinfunction "1_1") (pintype "passive"))
    )
    (net (code "52") (name "Net-(IC7A-+IN)") (class "Default")
      (node (ref "IC7") (pin "3") (pinfunction "+IN_3") (pintype "input"))
      (node (ref "R36") (pin "2") (pinfunction "2_2") (pintype "passive"))
      (node (ref "R39") (pin "2") (pinfunction "2_2") (pintype "passive"))
    )
    (net (code "53") (name "Net-(IC7A--IN)") (class "Default")
      (node (ref "IC7") (pin "2") (pinfunction "-IN_2") (pintype "input"))
      (node (ref "R43") (pin "2") (pinfunction "2_2") (pintype "passive"))
    )
    (net (code "54") (name "Net-(IC7A-OUT)") (class "Default")
      (node (ref "C28") (pin "1") (pinfunction "1_1") (pintype "passive"))
      (node (ref "IC7") (pin "1") (pinfunction "OUT_1") (pintype "output"))
      (node (ref "R37") (pin "2") (pinfunction "2_2") (pintype "passive"))
    )
    (net (code "55") (name "Net-(IC7B-+IN)") (class "Default")
      (node (ref "IC7") (pin "5") (pinfunction "+IN_5") (pintype "input"))
      (node (ref "R34") (pin "2") (pinfunction "2_2") (pintype "passive"))
      (node (ref "R35") (pin "1") (pinfunction "1_1") (pintype "passive"))
    )
    (net (code "56") (name "Net-(IC7B--IN)") (class "Default")
      (node (ref "C29") (pin "1") (pinfunction "1_1") (pintype "passive"))
      (node (ref "IC7") (pin "6") (pinfunction "-IN_6") (pintype "input"))
      (node (ref "R38") (pin "1") (pinfunction "1_1") (pintype "passive"))
      (node (ref "R41") (pin "2") (pinfunction "2_2") (pintype "passive"))
    )
    (net (code "57") (name "Net-(IC8-CAP+)") (class "Default")
      (node (ref "C34") (pin "+") (pinfunction "+_+") (pintype "passive"))
      (node (ref "IC8") (pin "2") (pinfunction "CAP+_2") (pintype "bidirectional"))
    )
    (net (code "58") (name "Net-(IC8-CAP-)") (class "Default")
      (node (ref "C34") (pin "-") (pinfunction "-_-") (pintype "passive"))
      (node (ref "IC8") (pin "4") (pinfunction "CAP-_4") (pintype "bidirectional"))
    )
    (net (code "59") (name "Net-(IC9A-+IN)") (class "Default")
      (node (ref "IC9") (pin "3") (pinfunction "+IN_3") (pintype "input"))
      (node (ref "R46") (pin "2") (pinfunction "2_2") (pintype "passive"))
      (node (ref "R49") (pin "2") (pinfunction "2_2") (pintype "passive"))
    )
    (net (code "60") (name "Net-(IC9A--IN)") (class "Default")
      (node (ref "IC9") (pin "2") (pinfunction "-IN_2") (pintype "input"))
      (node (ref "R53") (pin "2") (pinfunction "2_2") (pintype "passive"))
    )
    (net (code "61") (name "Net-(IC9A-OUT)") (class "Default")
      (node (ref "C36") (pin "1") (pinfunction "1_1") (pintype "passive"))
      (node (ref "IC9") (pin "1") (pinfunction "OUT_1") (pintype "output"))
      (node (ref "R47") (pin "2") (pinfunction "2_2") (pintype "passive"))
    )
    (net (code "62") (name "Net-(IC9B-+IN)") (class "Default")
      (node (ref "IC9") (pin "5") (pinfunction "+IN_5") (pintype "input"))
      (node (ref "R44") (pin "2") (pinfunction "2_2") (pintype "passive"))
      (node (ref "R45") (pin "1") (pinfunction "1_1") (pintype "passive"))
    )
    (net (code "63") (name "Net-(IC9B--IN)") (class "Default")
      (node (ref "C39") (pin "1") (pinfunction "1_1") (pintype "passive"))
      (node (ref "IC9") (pin "6") (pinfunction "-IN_6") (pintype "input"))
      (node (ref "R48") (pin "1") (pinfunction "1_1") (pintype "passive"))
      (node (ref "R51") (pin "2") (pinfunction "2_2") (pintype "passive"))
    )
    (net (code "64") (name "Net-(L2-Pad2)") (class "Default")
      (node (ref "L2") (pin "2") (pinfunction "2_2") (pintype "passive"))
      (node (ref "X1") (pin "1") (pinfunction "1_1") (pintype "passive"))
    )
    (net (code "65") (name "Net-(LED1-PadA)") (class "Default")
      (node (ref "LED1") (pin "A") (pinfunction "A_A") (pintype "passive"))
      (node (ref "R7") (pin "2") (pinfunction "2_2") (pintype "passive"))
    )
    (net (code "66") (name "Net-(Q2-PadS)") (class "Default")
      (node (ref "Q2") (pin "S") (pinfunction "S_S") (pintype "passive"))
      (node (ref "R20") (pin "2") (pinfunction "2_2") (pintype "passive"))
      (node (ref "R22") (pin "1") (pinfunction "1_1") (pintype "passive"))
      (node (ref "R23") (pin "1") (pinfunction "1_1") (pintype "passive"))
    )
    (net (code "67") (name "Net-(Q3-PadS)") (class "Default")
      (node (ref "Q3") (pin "S") (pinfunction "S_S") (pintype "passive"))
      (node (ref "R30") (pin "2") (pinfunction "2_2") (pintype "passive"))
      (node (ref "R32") (pin "1") (pinfunction "1_1") (pintype "passive"))
      (node (ref "R33") (pin "1") (pinfunction "1_1") (pintype "passive"))
    )
    (net (code "68") (name "Net-(Q4-PadS)") (class "Default")
      (node (ref "Q4") (pin "S") (pinfunction "S_S") (pintype "passive"))
      (node (ref "R40") (pin "2") (pinfunction "2_2") (pintype "passive"))
      (node (ref "R42") (pin "1") (pinfunction "1_1") (pintype "passive"))
      (node (ref "R43") (pin "1") (pinfunction "1_1") (pintype "passive"))
    )
    (net (code "69") (name "Net-(Q5-PadS)") (class "Default")
      (node (ref "Q5") (pin "S") (pinfunction "S_S") (pintype "passive"))
      (node (ref "R50") (pin "2") (pinfunction "2_2") (pintype "passive"))
      (node (ref "R52") (pin "1") (pinfunction "1_1") (pintype "passive"))
      (node (ref "R53") (pin "1") (pinfunction "1_1") (pintype "passive"))
    )
    (net (code "70") (name "Net-(X2A-S)") (class "Default")
      (node (ref "C14") (pin "1") (pinfunction "1_1") (pintype "passive"))
      (node (ref "Q2") (pin "D") (pinfunction "D_D") (pintype "passive"))
      (node (ref "X2") (pin "1") (pinfunction "S_1") (pintype "passive"))
    )
    (net (code "71") (name "Net-(X2E-S)") (class "Default")
      (node (ref "C33") (pin "1") (pinfunction "1_1") (pintype "passive"))
      (node (ref "Q5") (pin "D") (pinfunction "D_D") (pintype "passive"))
      (node (ref "X2") (pin "13") (pinfunction "S_13") (pintype "passive"))
    )
    (net (code "72") (name "Net-(X2I-S)") (class "Default")
      (node (ref "R45") (pin "2") (pinfunction "2_2") (pintype "passive"))
      (node (ref "X2") (pin "17") (pinfunction "S_17") (pintype "passive"))
    )
    (net (code "73") (name "Net-(X2J-S)") (class "Default")
      (node (ref "R18") (pin "2") (pinfunction "2_2") (pintype "passive"))
      (node (ref "X2") (pin "18") (pinfunction "S_18") (pintype "passive"))
    )
    (net (code "74") (name "Net-(X2K-S)") (class "Default")
      (node (ref "R28") (pin "2") (pinfunction "2_2") (pintype "passive"))
      (node (ref "X2") (pin "19") (pinfunction "S_19") (pintype "passive"))
    )
    (net (code "75") (name "Net-(X2L-S)") (class "Default")
      (node (ref "C19") (pin "1") (pinfunction "1_1") (pintype "passive"))
      (node (ref "Q3") (pin "D") (pinfunction "D_D") (pintype "passive"))
      (node (ref "X2") (pin "2") (pinfunction "S_2") (pintype "passive"))
    )
    (net (code "76") (name "Net-(X2R-S)") (class "Default")
      (node (ref "C25") (pin "1") (pinfunction "1_1") (pintype "passive"))
      (node (ref "Q4") (pin "D") (pinfunction "D_D") (pintype "passive"))
      (node (ref "X2") (pin "3") (pinfunction "S_3") (pintype "passive"))
    )
    (net (code "77") (name "Net-(X2T-S)") (class "Default")
      (node (ref "R48") (pin "2") (pinfunction "2_2") (pintype "passive"))
      (node (ref "X2") (pin "5") (pinfunction "S_5") (pintype "passive"))
    )
    (net (code "78") (name "Net-(X2U-S)") (class "Default")
      (node (ref "R15") (pin "2") (pinfunction "2_2") (pintype "passive"))
      (node (ref "X2") (pin "6") (pinfunction "S_6") (pintype "passive"))
    )
    (net (code "79") (name "Net-(X2V-S)") (class "Default")
      (node (ref "R25") (pin "2") (pinfunction "2_2") (pintype "passive"))
      (node (ref "X2") (pin "7") (pinfunction "S_7") (pintype "passive"))
    )
    (net (code "80") (name "Net-(X2W-S)") (class "Default")
      (node (ref "R35") (pin "2") (pinfunction "2_2") (pintype "passive"))
      (node (ref "X2") (pin "8") (pinfunction "S_8") (pintype "passive"))
    )
    (net (code "81") (name "Net-(X2X-S)") (class "Default")
      (node (ref "R38") (pin "2") (pinfunction "2_2") (pintype "passive"))
      (node (ref "X2") (pin "9") (pinfunction "S_9") (pintype "passive"))
    )
    (net (code "82") (name "SCK") (class "Default")
      (node (ref "IC2") (pin "17") (pinfunction "PB5(SCK)_17") (pintype "bidirectional"))
      (node (ref "IC6") (pin "14") (pinfunction "SCLK_14") (pintype "bidirectional"))
      (node (ref "JP1") (pin "3") (pinfunction "3_3") (pintype "passive"))
    )
    (net (code "83") (name "SYNC") (class "Default")
      (node (ref "IC2") (pin "13") (pinfunction "PB1(OC1A)_13") (pintype "bidirectional"))
      (node (ref "IC6") (pin "15") (pinfunction "SYNC_15") (pintype "bidirectional"))
    )
    (net (code "84") (name "VCC") (class "Default")
      (node (ref "C1") (pin "1") (pinfunction "1_1") (pintype "passive"))
      (node (ref "C15") (pin "2") (pinfunction "2_2") (pintype "passive"))
      (node (ref "C2") (pin "+") (pinfunction "+_+") (pintype "passive"))
      (node (ref "C20") (pin "2") (pinfunction "2_2") (pintype "passive"))
      (node (ref "C27") (pin "2") (pinfunction "2_2") (pintype "passive"))
      (node (ref "C31") (pin "2") (pinfunction "2_2") (pintype "passive"))
      (node (ref "C32") (pin "+") (pinfunction "+_+") (pintype "passive"))
      (node (ref "C35") (pin "2") (pinfunction "2_2") (pintype "passive"))
      (node (ref "C4") (pin "1") (pinfunction "1_1") (pintype "passive"))
      (node (ref "C6") (pin "2") (pinfunction "2_2") (pintype "passive"))
      (node (ref "IC1") (pin "2") (pinfunction "V_2") (pintype "power_in"))
      (node (ref "IC2") (pin "18") (pinfunction "AVCC_18") (pintype "power_in"))
      (node (ref "IC4") (pin "8") (pinfunction "V+_8") (pintype "power_in"))
      (node (ref "IC5") (pin "8") (pinfunction "V+_8") (pintype "power_in"))
      (node (ref "IC7") (pin "8") (pinfunction "V+_8") (pintype "power_in"))
      (node (ref "IC8") (pin "8") (pinfunction "V+_8") (pintype "bidirectional"))
      (node (ref "IC9") (pin "8") (pinfunction "V+_8") (pintype "power_in"))
      (node (ref "L1") (pin "2") (pinfunction "2_2") (pintype "passive"))
      (node (ref "R1") (pin "1") (pinfunction "1_1") (pintype "passive"))
    )
    (net (code "85") (name "VREF") (class "Default")
      (node (ref "C26") (pin "1") (pinfunction "1_1") (pintype "passive"))
      (node (ref "C5") (pin "1") (pinfunction "1_1") (pintype "passive"))
      (node (ref "C7") (pin "2") (pinfunction "2_2") (pintype "passive"))
      (node (ref "IC1") (pin "6") (pinfunction "OUT_6") (pintype "output"))
      (node (ref "IC2") (pin "20") (pinfunction "AREF_20") (pintype "passive"))
      (node (ref "IC6") (pin "7") (pinfunction "REF_AB_7") (pintype "bidirectional"))
      (node (ref "IC6") (pin "8") (pinfunction "REF_CD_8") (pintype "bidirectional"))
    )
    (net (code "86") (name "unconnected-(IC2-ADC6-Pad19)") (class "Default")
      (node (ref "IC2") (pin "19") (pinfunction "ADC6_19") (pintype "bidirectional"))
    )
    (net (code "87") (name "unconnected-(IC2-ADC7-Pad22)") (class "Default")
      (node (ref "IC2") (pin "22") (pinfunction "ADC7_22") (pintype "bidirectional"))
    )
    (net (code "88") (name "unconnected-(IC2-PC4(ADC4{slash}SDA)-Pad27)") (class "Default")
      (node (ref "IC2") (pin "27") (pinfunction "PC4(ADC4/SDA)_27") (pintype "bidirectional"))
    )
    (net (code "89") (name "unconnected-(IC2-PC5(ADC5{slash}SCL)-Pad28)") (class "Default")
      (node (ref "IC2") (pin "28") (pinfunction "PC5(ADC5/SCL)_28") (pintype "bidirectional"))
    )
    (net (code "90") (name "unconnected-(IC2-PD6(AIN0)-Pad10)") (class "Default")
      (node (ref "IC2") (pin "10") (pinfunction "PD6(AIN0)_10") (pintype "bidirectional"))
    )
    (net (code "91") (name "unconnected-(IC2-PD7(AIN1)-Pad11)") (class "Default")
      (node (ref "IC2") (pin "11") (pinfunction "PD7(AIN1)_11") (pintype "bidirectional"))
    )
    (net (code "92") (name "unconnected-(IC3-3V3OUT-Pad17)") (class "Default")
      (node (ref "IC3") (pin "17") (pinfunction "3V3OUT_17") (pintype "output"))
    )
    (net (code "93") (name "unconnected-(IC3-CBUS0-Pad23)") (class "Default")
      (node (ref "IC3") (pin "23") (pinfunction "CBUS0_23") (pintype "bidirectional"))
    )
    (net (code "94") (name "unconnected-(IC3-CBUS1-Pad22)") (class "Default")
      (node (ref "IC3") (pin "22") (pinfunction "CBUS1_22") (pintype "bidirectional"))
    )
    (net (code "95") (name "unconnected-(IC3-CBUS2-Pad13)") (class "Default")
      (node (ref "IC3") (pin "13") (pinfunction "CBUS2_13") (pintype "bidirectional"))
    )
    (net (code "96") (name "unconnected-(IC3-CBUS3-Pad14)") (class "Default")
      (node (ref "IC3") (pin "14") (pinfunction "CBUS3_14") (pintype "bidirectional"))
    )
    (net (code "97") (name "unconnected-(IC3-CBUS4-Pad12)") (class "Default")
      (node (ref "IC3") (pin "12") (pinfunction "CBUS4_12") (pintype "bidirectional"))
    )
    (net (code "98") (name "unconnected-(IC3-OSCI-Pad27)") (class "Default")
      (node (ref "IC3") (pin "27") (pinfunction "OSCI_27") (pintype "input"))
    )
    (net (code "99") (name "unconnected-(IC3-OSCO-Pad28)") (class "Default")
      (node (ref "IC3") (pin "28") (pinfunction "OSCO_28") (pintype "output"))
    )
    (net (code "100") (name "unconnected-(IC3-~{CTS}-Pad11)") (class "Default")
      (node (ref "IC3") (pin "11") (pinfunction "~{CTS}_11") (pintype "input"))
    )
    (net (code "101") (name "unconnected-(IC3-~{DCD}-Pad10)") (class "Default")
      (node (ref "IC3") (pin "10") (pinfunction "~{DCD}_10") (pintype "input"))
    )
    (net (code "102") (name "unconnected-(IC3-~{DSR}-Pad9)") (class "Default")
      (node (ref "IC3") (pin "9") (pinfunction "~{DSR}_9") (pintype "input"))
    )
    (net (code "103") (name "unconnected-(IC3-~{DTR}-Pad2)") (class "Default")
      (node (ref "IC3") (pin "2") (pinfunction "~{DTR}_2") (pintype "output"))
    )
    (net (code "104") (name "unconnected-(IC3-~{RI}-Pad6)") (class "Default")
      (node (ref "IC3") (pin "6") (pinfunction "~{RI}_6") (pintype "input"))
    )
    (net (code "105") (name "unconnected-(IC3-~{RTS}-Pad3)") (class "Default")
      (node (ref "IC3") (pin "3") (pinfunction "~{RTS}_3") (pintype "output"))
    )
    (net (code "106") (name "unconnected-(IC6-SDO-Pad16)") (class "Default")
      (node (ref "IC6") (pin "16") (pinfunction "SDO_16") (pintype "bidirectional"))
    )
    (net (code "107") (name "unconnected-(IC8-FC-Pad1)") (class "Default")
      (node (ref "IC8") (pin "1") (pinfunction "FC_1") (pintype "bidirectional"))
    )
    (net (code "108") (name "unconnected-(IC8-LV-Pad6)") (class "Default")
      (node (ref "IC8") (pin "6") (pinfunction "LV_6") (pintype "bidirectional"))
    )
    (net (code "109") (name "unconnected-(IC8-OSC-Pad7)") (class "Default")
      (node (ref "IC8") (pin "7") (pinfunction "OSC_7") (pintype "bidirectional"))
    )
    (net (code "110") (name "unconnected-(X2M-S-Pad20)") (class "Default")
      (node (ref "X2") (pin "20") (pinfunction "S_20") (pintype "passive"))
    )
    (net (code "111") (name "unconnected-(X2O-S-Pad22)") (class "Default")
      (node (ref "X2") (pin "22") (pinfunction "S_22") (pintype "passive"))
    )
    (net (code "112") (name "unconnected-(X2P-S-Pad23)") (class "Default")
      (node (ref "X2") (pin "23") (pinfunction "S_23") (pintype "passive"))
    )
  )
)
